# rgb_pinout.net
KiCad netlist of a schematic drawn in EAGLE
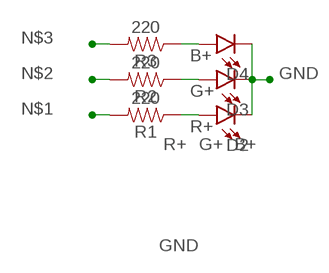
[diagram p0: schematic, sheet 1]

(export (version "E")
  (design (tool "Eeschema 10.0.6"))
  (components
    (comp (ref "D2")
      (value "LED-3MM-NO_SILK")
      (footprint "eagle-import:LED_3MM-NS")
      (libsource (lib "eagle-import") (part "LED-3MM-NO_SILK"))
    )
    (comp (ref "D3")
      (value "LED-3MM-NO_SILK")
      (footprint "eagle-import:LED_3MM-NS")
      (libsource (lib "eagle-import") (part "LED-3MM-NO_SILK"))
    )
    (comp (ref "D4")
      (value "LED-3MM-NO_SILK")
      (footprint "eagle-import:LED_3MM-NS")
      (libsource (lib "eagle-import") (part "LED-3MM-NO_SILK"))
    )
    (comp (ref "R1")
      (value "220")
      (footprint "eagle-import:0603")
      (libsource (lib "eagle-import") (part "220OHM-0603-1/10W-1%"))
    )
    (comp (ref "R2")
      (value "220")
      (footprint "eagle-import:0603")
      (libsource (lib "eagle-import") (part "220OHM-0603-1/10W-1%"))
    )
    (comp (ref "R3")
      (value "220")
      (footprint "eagle-import:0603")
      (libsource (lib "eagle-import") (part "220OHM-0603-1/10W-1%"))
    )
  )
  (nets
    (net (code "1") (name "/B+") (class "Default")
      (node (ref "D4") (pin "A") (pinfunction "A_A") (pintype "passive"))
      (node (ref "R3") (pin "1") (pinfunction "1_1") (pintype "passive"))
    )
    (net (code "2") (name "/G+") (class "Default")
      (node (ref "D3") (pin "A") (pinfunction "A_A") (pintype "passive"))
      (node (ref "R2") (pin "1") (pinfunction "1_1") (pintype "passive"))
    )
    (net (code "3") (name "/GND") (class "Default")
      (node (ref "D2") (pin "K") (pinfunction "C_K") (pintype "passive"))
      (node (ref "D3") (pin "K") (pinfunction "C_K") (pintype "passive"))
      (node (ref "D4") (pin "K") (pinfunction "C_K") (pintype "passive"))
    )
    (net (code "4") (name "/N$1") (class "Default")
      (node (ref "R1") (pin "2") (pinfunction "2_2") (pintype "passive"))
    )
    (net (code "5") (name "/N$2") (class "Default")
      (node (ref "R2") (pin "2") (pinfunction "2_2") (pintype "passive"))
    )
    (net (code "6") (name "/N$3") (class "Default")
      (node (ref "R3") (pin "2") (pinfunction "2_2") (pintype "passive"))
    )
    (net (code "7") (name "/R+") (class "Default")
      (node (ref "D2") (pin "A") (pinfunction "A_A") (pintype "passive"))
      (node (ref "R1") (pin "1") (pinfunction "1_1") (pintype "passive"))
    )
  )
)
